# PCB_Arduino1.net
KiCad netlist of a schematic drawn in EAGLE
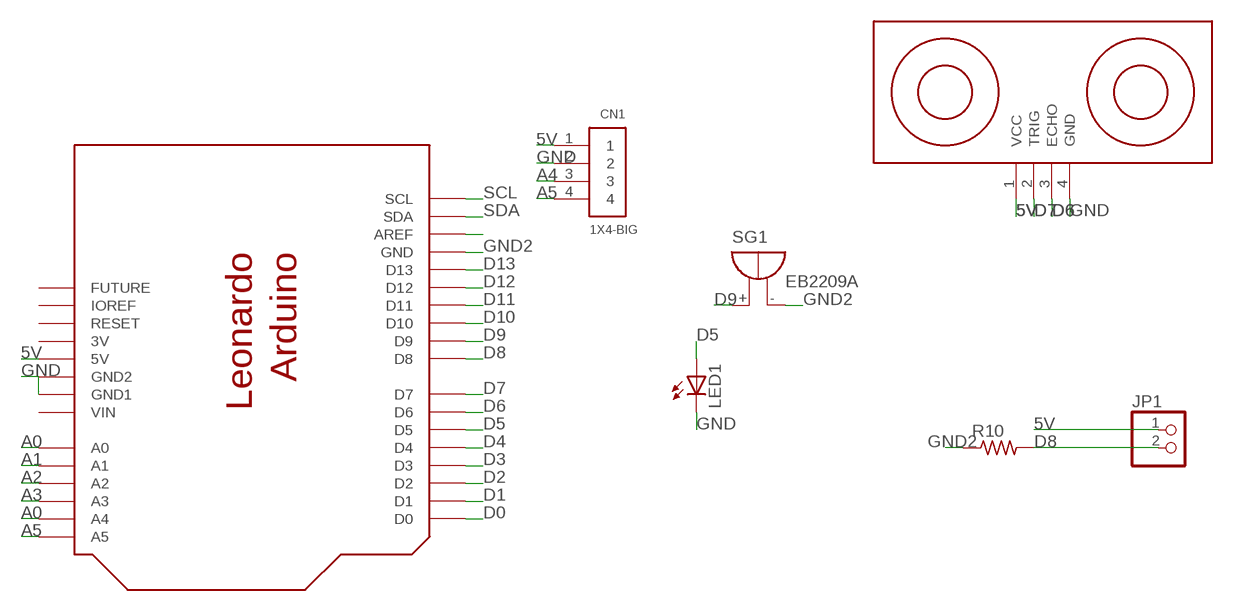
[diagram p0: schematic, sheet 1]

(export (version "E")
  (design (tool "Eeschema 10.0.6"))
  (components
    (comp (ref "CN1")
      (value "1X4-BIG")
      (footprint "eagle-import:1X04-BIG")
      (libsource (lib "eagle-import") (part "1X4-BIG"))
    )
    (comp (ref "JP1")
      (value "PINHD-1X2")
      (footprint "eagle-import:1X02")
      (libsource (lib "eagle-import") (part "PINHD-1X2"))
    )
    (comp (ref "LED1")
      (value "LEDB152")
      (footprint "eagle-import:Q62902-B152")
      (libsource (lib "eagle-import") (part "LEDB152"))
    )
    (comp (ref "R10")
      (value "R-US_0204/7")
      (footprint "eagle-import:0204_7")
      (libsource (lib "eagle-import") (part "R-US_0204/7"))
    )
    (comp (ref "SG1")
      (value "EB2209A")
      (footprint "eagle-import:EB2209A")
      (libsource (lib "eagle-import") (part "EB2209A"))
    )
    (comp (ref "U$1")
      (value "ARDUINO_LEONARDO")
      (footprint "eagle-import:ARDUINO_LEONARDO")
      (libsource (lib "eagle-import") (part "ARDUINO_LEONARDO"))
    )
    (comp (ref "U$2")
      (value "ULTRASONIC-HC-SR04")
      (footprint "eagle-import:ULTRASONIC-HC-SR04")
      (libsource (lib "eagle-import") (part "ULTRASONIC-HC-SR04"))
    )
  )
  (nets
    (net (code "1") (name "/3V") (class "Default")
      (node (ref "U$1") (pin "3V") (pinfunction "3V_3V") (pintype "power_in"))
    )
    (net (code "2") (name "/5V") (class "Default")
      (node (ref "CN1") (pin "1") (pinfunction "1_1") (pintype "bidirectional"))
      (node (ref "JP1") (pin "1") (pinfunction "1_1") (pintype "passive"))
      (node (ref "U$1") (pin "5V") (pinfunction "5V_5V") (pintype "power_in"))
      (node (ref "U$2") (pin "1") (pinfunction "VCC_1") (pintype "power_in"))
    )
    (net (code "3") (name "/A0") (class "Default")
      (node (ref "U$1") (pin "A0") (pinfunction "A0_A0") (pintype "bidirectional"))
    )
    (net (code "4") (name "/A1") (class "Default")
      (node (ref "U$1") (pin "A1") (pinfunction "A1_A1") (pintype "bidirectional"))
    )
    (net (code "5") (name "/A2") (class "Default")
      (node (ref "U$1") (pin "A2") (pinfunction "A2_A2") (pintype "bidirectional"))
    )
    (net (code "6") (name "/A3") (class "Default")
      (node (ref "U$1") (pin "A3") (pinfunction "A3_A3") (pintype "bidirectional"))
    )
    (net (code "7") (name "/A4") (class "Default")
      (node (ref "CN1") (pin "3") (pinfunction "3_3") (pintype "bidirectional"))
      (node (ref "U$1") (pin "A4") (pinfunction "A4_A4") (pintype "bidirectional"))
    )
    (net (code "8") (name "/A5") (class "Default")
      (node (ref "CN1") (pin "4") (pinfunction "4_4") (pintype "bidirectional"))
      (node (ref "U$1") (pin "A5") (pinfunction "A5_A5") (pintype "bidirectional"))
    )
    (net (code "9") (name "/D0") (class "Default")
      (node (ref "U$1") (pin "D0") (pinfunction "D0_D0") (pintype "bidirectional"))
    )
    (net (code "10") (name "/D1") (class "Default")
      (node (ref "U$1") (pin "D1") (pinfunction "D1_D1") (pintype "bidirectional"))
    )
    (net (code "11") (name "/D2") (class "Default")
      (node (ref "U$1") (pin "D2") (pinfunction "D2_D2") (pintype "bidirectional"))
    )
    (net (code "12") (name "/D3") (class "Default")
      (node (ref "U$1") (pin "D3") (pinfunction "D3_D3") (pintype "bidirectional"))
    )
    (net (code "13") (name "/D4") (class "Default")
      (node (ref "U$1") (pin "D4") (pinfunction "D4_D4") (pintype "bidirectional"))
    )
    (net (code "14") (name "/D5") (class "Default")
      (node (ref "LED1") (pin "A") (pinfunction "A_A") (pintype "passive"))
      (node (ref "U$1") (pin "D5") (pinfunction "D5_D5") (pintype "bidirectional"))
    )
    (net (code "15") (name "/D6") (class "Default")
      (node (ref "U$1") (pin "D6") (pinfunction "D6_D6") (pintype "bidirectional"))
      (node (ref "U$2") (pin "3") (pinfunction "ECHO_3") (pintype "output"))
    )
    (net (code "16") (name "/D7") (class "Default")
      (node (ref "U$1") (pin "D7") (pinfunction "D7_D7") (pintype "bidirectional"))
      (node (ref "U$2") (pin "2") (pinfunction "TRIG_2") (pintype "input"))
    )
    (net (code "17") (name "/D8") (class "Default")
      (node (ref "JP1") (pin "2") (pinfunction "2_2") (pintype "passive"))
      (node (ref "R10") (pin "2") (pinfunction "2_2") (pintype "passive"))
      (node (ref "U$1") (pin "D8") (pinfunction "D8_D8") (pintype "bidirectional"))
    )
    (net (code "18") (name "/D9") (class "Default")
      (node (ref "SG1") (pin "+") (pinfunction "+_+") (pintype "passive"))
      (node (ref "U$1") (pin "D9") (pinfunction "D9_D9") (pintype "bidirectional"))
    )
    (net (code "19") (name "/D10") (class "Default")
      (node (ref "U$1") (pin "D10") (pinfunction "D10_D10") (pintype "bidirectional"))
    )
    (net (code "20") (name "/D11") (class "Default")
      (node (ref "U$1") (pin "D11") (pinfunction "D11_D11") (pintype "bidirectional"))
    )
    (net (code "21") (name "/D12") (class "Default")
      (node (ref "U$1") (pin "D12") (pinfunction "D12_D12") (pintype "bidirectional"))
    )
    (net (code "22") (name "/D13") (class "Default")
      (node (ref "U$1") (pin "D13") (pinfunction "D13_D13") (pintype "bidirectional"))
    )
    (net (code "23") (name "/GND") (class "Default")
      (node (ref "CN1") (pin "2") (pinfunction "2_2") (pintype "bidirectional"))
      (node (ref "LED1") (pin "K") (pinfunction "C_K") (pintype "passive"))
      (node (ref "U$1") (pin "GND$2") (pinfunction "GND2_GND$2") (pintype "power_in"))
      (node (ref "U$1") (pin "GND$3") (pinfunction "GND1_GND$3") (pintype "power_in"))
      (node (ref "U$2") (pin "4") (pinfunction "GND_4") (pintype "power_in"))
    )
    (net (code "24") (name "/GND2") (class "Default")
      (node (ref "R10") (pin "1") (pinfunction "1_1") (pintype "passive"))
      (node (ref "SG1") (pin "-") (pinfunction "-_-") (pintype "passive"))
      (node (ref "U$1") (pin "GND") (pinfunction "GND_GND") (pintype "power_in"))
    )
    (net (code "25") (name "/SCL") (class "Default")
      (node (ref "U$1") (pin "SCL") (pinfunction "SCL_SCL") (pintype "bidirectional"))
    )
    (net (code "26") (name "/SDA") (class "Default")
      (node (ref "U$1") (pin "SDA") (pinfunction "SDA_SDA") (pintype "bidirectional"))
    )
    (net (code "27") (name "/VIN") (class "Default")
      (node (ref "U$1") (pin "VIN") (pinfunction "VIN_VIN") (pintype "power_in"))
    )
    (net (code "28") (name "unconnected-(U$1-FUTURE-PadRESERVED)") (class "Default")
      (node (ref "U$1") (pin "RESERVED") (pinfunction "FUTURE_RESERVED") (pintype "bidirectional"))
    )
    (net (code "29") (name "unconnected-(U$1-PadAREF)") (class "Default")
      (node (ref "U$1") (pin "AREF") (pinfunction "AREF_AREF") (pintype "bidirectional"))
    )
    (net (code "30") (name "unconnected-(U$1-PadIOREF)") (class "Default")
      (node (ref "U$1") (pin "IOREF") (pinfunction "IOREF_IOREF") (pintype "bidirectional"))
    )
    (net (code "31") (name "unconnected-(U$1-PadRESET)") (class "Default")
      (node (ref "U$1") (pin "RESET") (pinfunction "RESET_RESET") (pintype "bidirectional"))
    )
  )
)
